# color.net
KiCad netlist of a schematic drawn in EAGLE
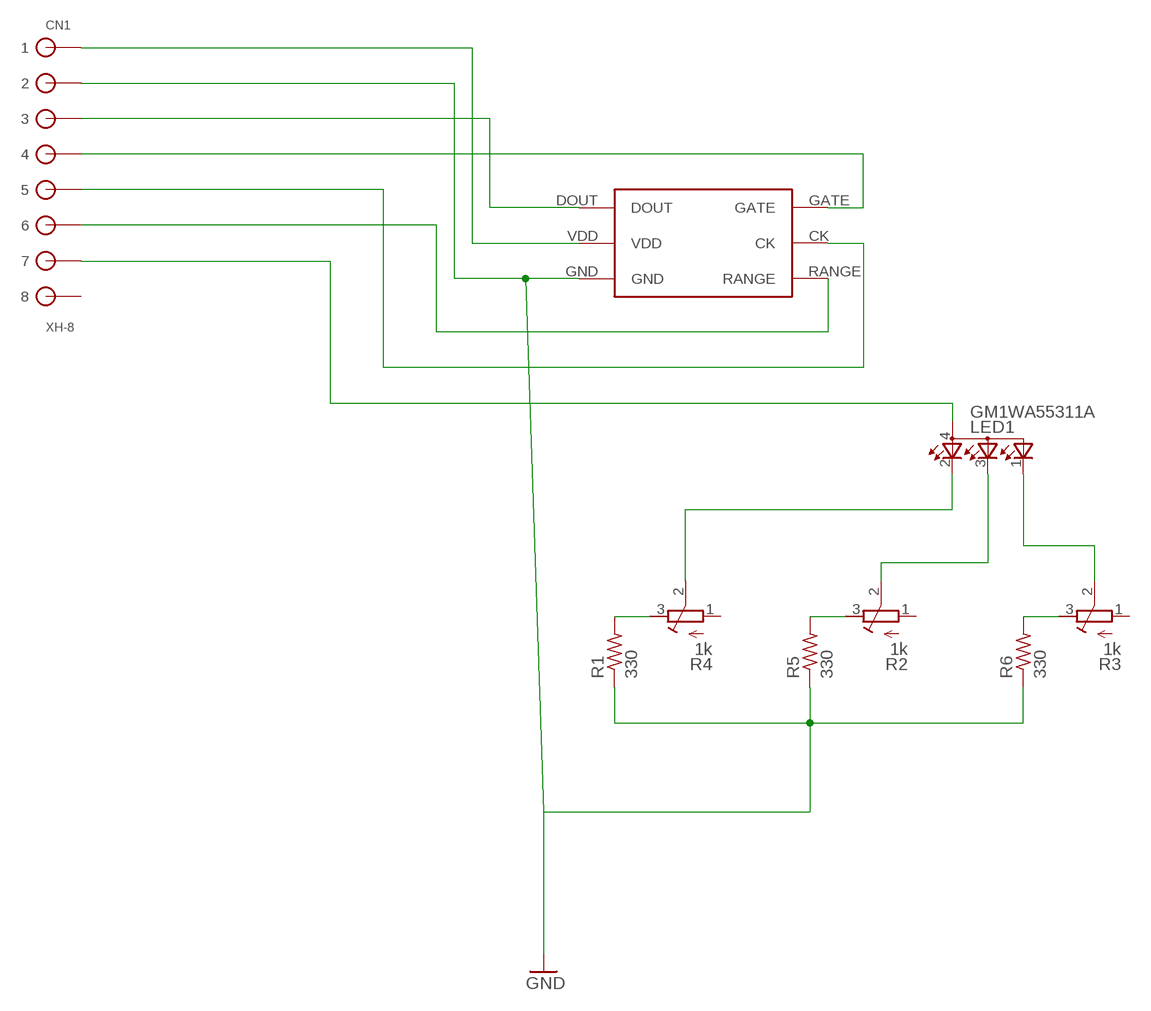
[diagram p0: schematic, sheet 1]

(export (version "E")
  (design (tool "Eeschema 10.0.6"))
  (components
    (comp (ref "CN1")
      (value "XH-8")
      (footprint "eagle-import:CON8")
      (libsource (lib "eagle-import") (part "XH-8"))
    )
    (comp (ref "LED1")
      (value "GM1WA55311A")
      (footprint "eagle-import:GM1WA55311A")
      (libsource (lib "eagle-import") (part "GM1WA55311A"))
    )
    (comp (ref "R1")
      (value "330")
      (footprint "eagle-import:R0805")
      (libsource (lib "eagle-import") (part "R-US_R0805"))
    )
    (comp (ref "R2")
      (value "1k")
      (footprint "eagle-import:RTRIM3339P")
      (libsource (lib "eagle-import") (part "R-TRIMM3339P"))
    )
    (comp (ref "R3")
      (value "1k")
      (footprint "eagle-import:RTRIM3339P")
      (libsource (lib "eagle-import") (part "R-TRIMM3339P"))
    )
    (comp (ref "R4")
      (value "1k")
      (footprint "eagle-import:RTRIM3339P")
      (libsource (lib "eagle-import") (part "R-TRIMM3339P"))
    )
    (comp (ref "R5")
      (value "330")
      (footprint "eagle-import:R0805")
      (libsource (lib "eagle-import") (part "R-US_R0805"))
    )
    (comp (ref "R6")
      (value "330")
      (footprint "eagle-import:R0805")
      (libsource (lib "eagle-import") (part "R-US_R0805"))
    )
    (comp (ref "U$1")
      (value "S9706")
      (footprint "eagle-import:S9706")
      (libsource (lib "eagle-import") (part "S9706"))
    )
  )
  (nets
    (net (code "1") (name "GND") (class "Default")
      (node (ref "CN1") (pin "P$2") (pinfunction "2_P$2") (pintype "bidirectional"))
      (node (ref "R1") (pin "1") (pinfunction "1_1") (pintype "passive"))
      (node (ref "R5") (pin "1") (pinfunction "1_1") (pintype "passive"))
      (node (ref "R6") (pin "1") (pinfunction "1_1") (pintype "passive"))
      (node (ref "U$1") (pin "GND") (pinfunction "GND_GND") (pintype "bidirectional"))
    )
    (net (code "2") (name "Net-(CN1-1)") (class "Default")
      (node (ref "CN1") (pin "P$1") (pinfunction "1_P$1") (pintype "bidirectional"))
      (node (ref "U$1") (pin "VDD") (pinfunction "VDD_VDD") (pintype "bidirectional"))
    )
    (net (code "3") (name "Net-(CN1-3)") (class "Default")
      (node (ref "CN1") (pin "P$3") (pinfunction "3_P$3") (pintype "bidirectional"))
      (node (ref "U$1") (pin "DOUT") (pinfunction "DOUT_DOUT") (pintype "bidirectional"))
    )
    (net (code "4") (name "Net-(CN1-4)") (class "Default")
      (node (ref "CN1") (pin "P$4") (pinfunction "4_P$4") (pintype "bidirectional"))
      (node (ref "U$1") (pin "GATE") (pinfunction "GATE_GATE") (pintype "bidirectional"))
    )
    (net (code "5") (name "Net-(CN1-5)") (class "Default")
      (node (ref "CN1") (pin "P$5") (pinfunction "5_P$5") (pintype "bidirectional"))
      (node (ref "U$1") (pin "CK") (pinfunction "CK_CK") (pintype "bidirectional"))
    )
    (net (code "6") (name "Net-(CN1-6)") (class "Default")
      (node (ref "CN1") (pin "P$6") (pinfunction "6_P$6") (pintype "bidirectional"))
      (node (ref "U$1") (pin "RANGE") (pinfunction "RANGE_RANGE") (pintype "bidirectional"))
    )
    (net (code "7") (name "Net-(CN1-7)") (class "Default")
      (node (ref "CN1") (pin "P$7") (pinfunction "7_P$7") (pintype "bidirectional"))
      (node (ref "LED1") (pin "4") (pinfunction "A_4") (pintype "passive"))
    )
    (net (code "8") (name "Net-(LED1-CBLUE)") (class "Default")
      (node (ref "LED1") (pin "3") (pinfunction "CBLUE_3") (pintype "passive"))
      (node (ref "R2") (pin "2") (pinfunction "S_2") (pintype "passive"))
    )
    (net (code "9") (name "Net-(LED1-CGREEN)") (class "Default")
      (node (ref "LED1") (pin "1") (pinfunction "CGREEN_1") (pintype "passive"))
      (node (ref "R3") (pin "2") (pinfunction "S_2") (pintype "passive"))
    )
    (net (code "10") (name "Net-(LED1-CRED)") (class "Default")
      (node (ref "LED1") (pin "2") (pinfunction "CRED_2") (pintype "passive"))
      (node (ref "R4") (pin "2") (pinfunction "S_2") (pintype "passive"))
    )
    (net (code "11") (name "Net-(R2-E)") (class "Default")
      (node (ref "R2") (pin "3") (pinfunction "E_3") (pintype "passive"))
      (node (ref "R5") (pin "2") (pinfunction "2_2") (pintype "passive"))
    )
    (net (code "12") (name "Net-(R3-E)") (class "Default")
      (node (ref "R3") (pin "3") (pinfunction "E_3") (pintype "passive"))
      (node (ref "R6") (pin "2") (pinfunction "2_2") (pintype "passive"))
    )
    (net (code "13") (name "Net-(R4-E)") (class "Default")
      (node (ref "R1") (pin "2") (pinfunction "2_2") (pintype "passive"))
      (node (ref "R4") (pin "3") (pinfunction "E_3") (pintype "passive"))
    )
    (net (code "14") (name "unconnected-(CN1-8-PadP$8)") (class "Default")
      (node (ref "CN1") (pin "P$8") (pinfunction "8_P$8") (pintype "bidirectional"))
    )
    (net (code "15") (name "unconnected-(R2-A-Pad1)") (class "Default")
      (node (ref "R2") (pin "1") (pinfunction "A_1") (pintype "passive"))
    )
    (net (code "16") (name "unconnected-(R3-A-Pad1)") (class "Default")
      (node (ref "R3") (pin "1") (pinfunction "A_1") (pintype "passive"))
    )
    (net (code "17") (name "unconnected-(R4-A-Pad1)") (class "Default")
      (node (ref "R4") (pin "1") (pinfunction "A_1") (pintype "passive"))
    )
  )
)
